# ASB.net
KiCad netlist of a schematic drawn in Altium Designer
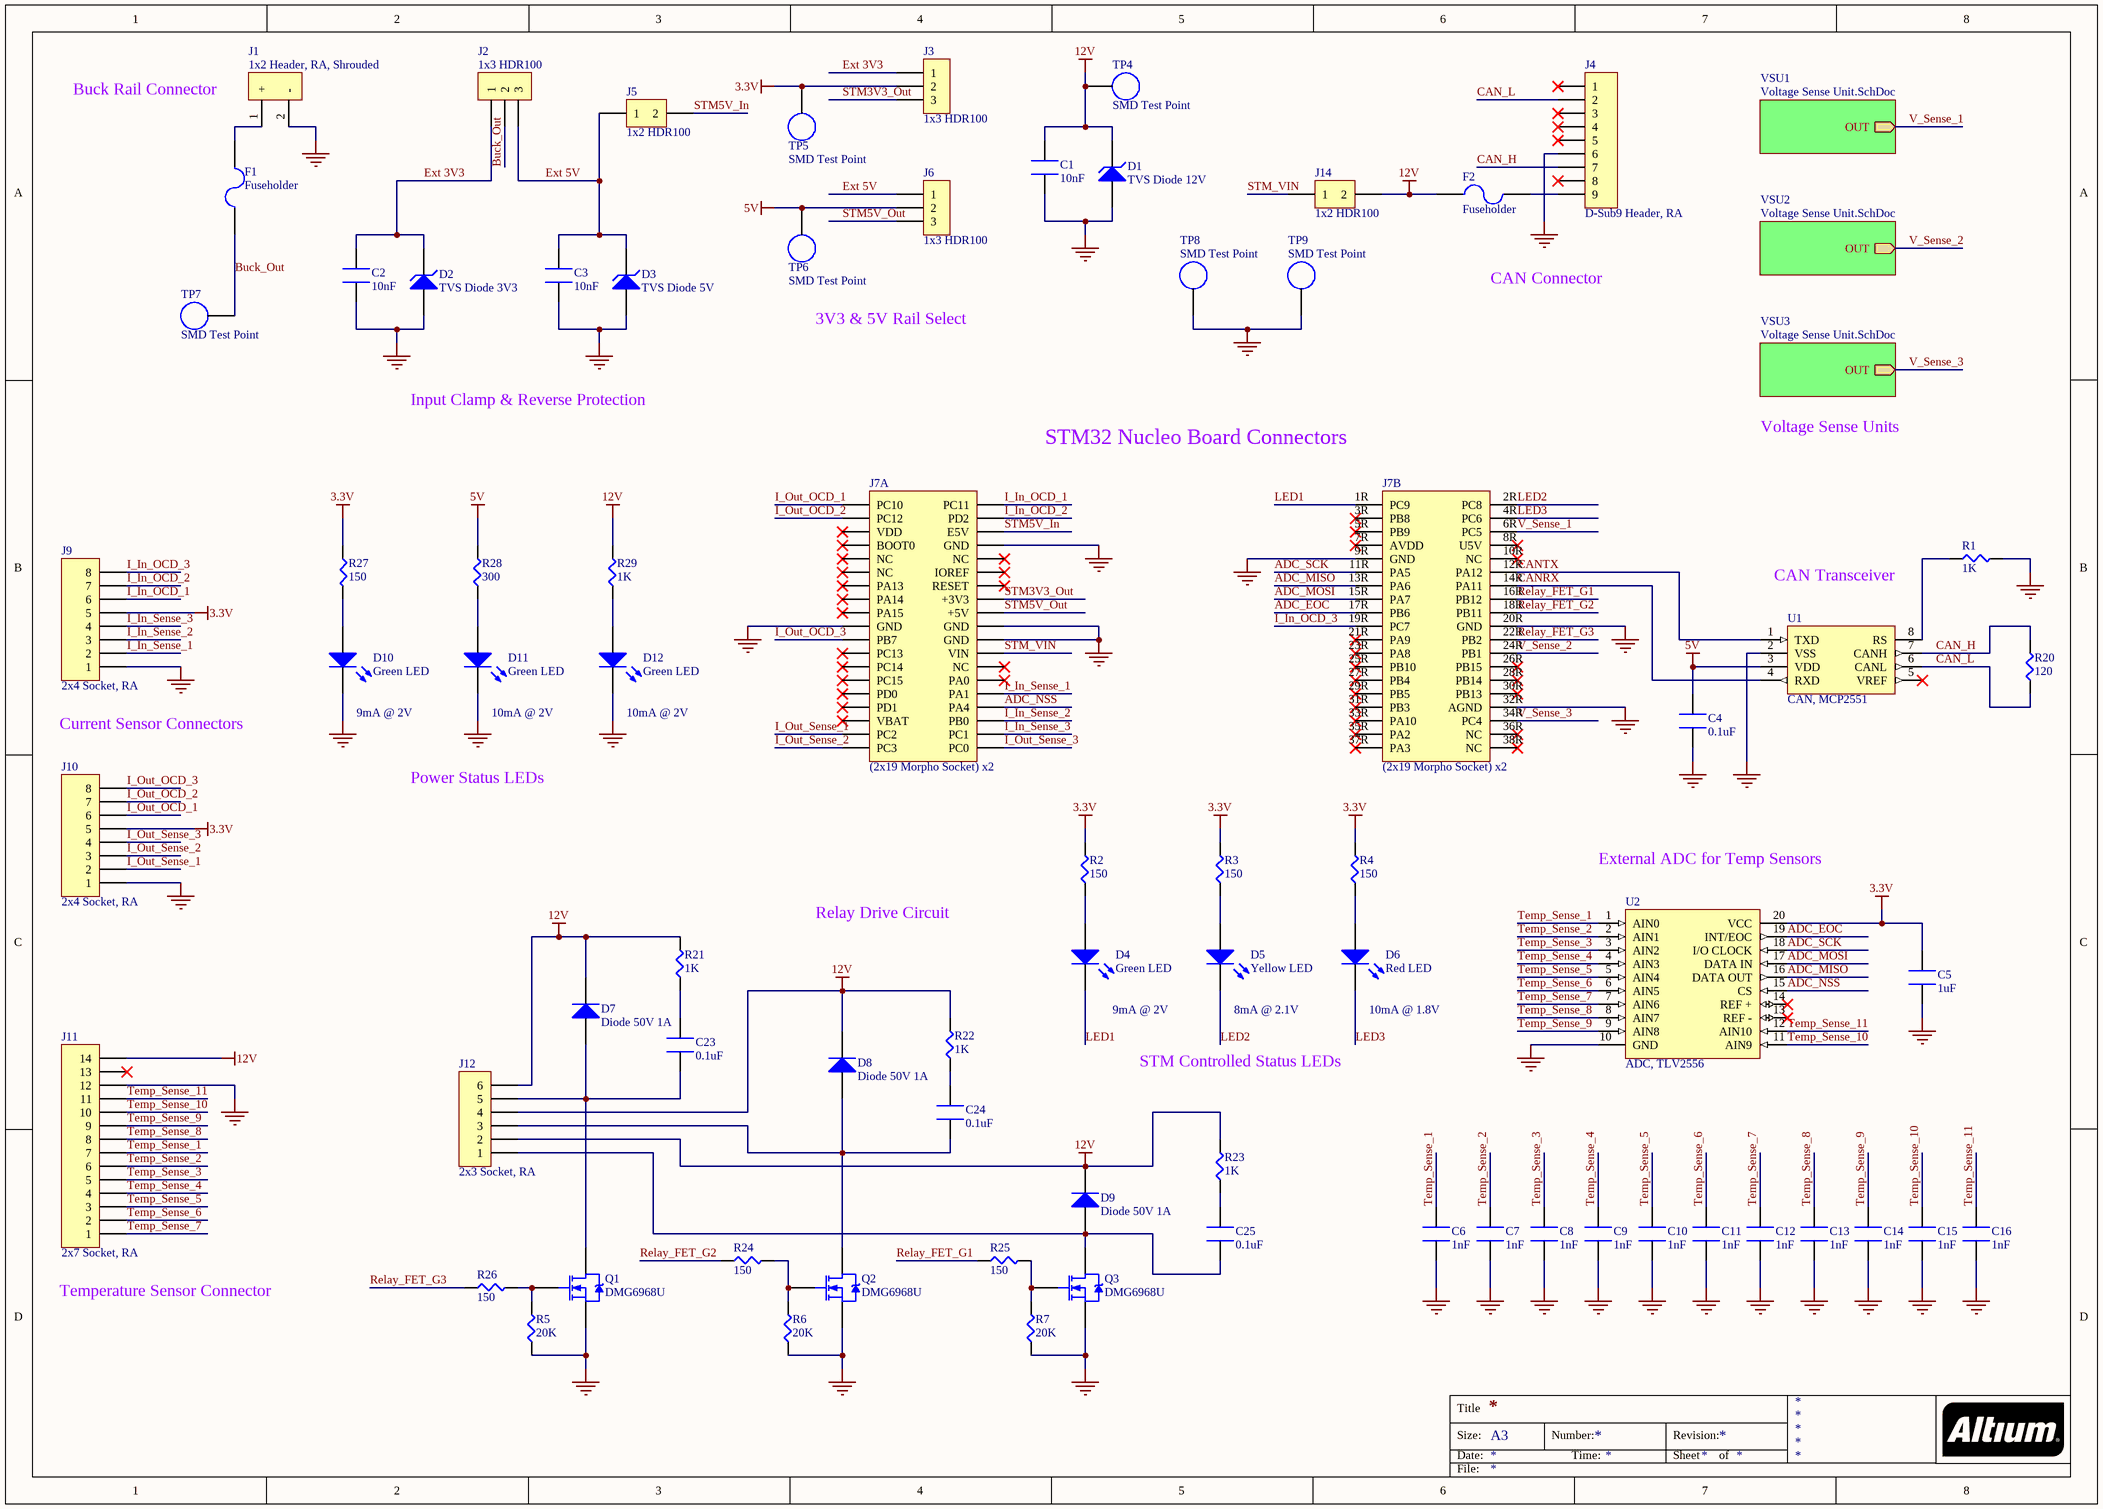
[diagram p0: ASB.SchDoc]

(export (version "E")
  (design (tool "Eeschema 10.0.6"))
  (components
    (comp (ref "C1")
      (value "10nF")
      (footprint "C0805")
      (description "Cap Ceramic 0.01uF 50V X7R 10% SMD 0805 125C Paper T/R")
      (fields
        (field (name "MANUFACTURER") "Samsung")
        (field (name "MANUFACTURER PART NUMBER") "CL21B103KBANNNC")
      )
      (libsource (lib "ASB") (part "CL21B103KBANNNC"))
    )
    (comp (ref "C2")
      (value "10nF")
      (footprint "C0805")
      (description "Cap Ceramic 0.01uF 50V X7R 10% SMD 0805 125C Paper T/R")
      (fields
        (field (name "MANUFACTURER") "Samsung")
        (field (name "MANUFACTURER PART NUMBER") "CL21B103KBANNNC")
      )
      (libsource (lib "ASB") (part "CL21B103KBANNNC"))
    )
    (comp (ref "C3")
      (value "10nF")
      (footprint "C0805")
      (description "Cap Ceramic 0.01uF 50V X7R 10% SMD 0805 125C Paper T/R")
      (fields
        (field (name "MANUFACTURER") "Samsung")
        (field (name "MANUFACTURER PART NUMBER") "CL21B103KBANNNC")
      )
      (libsource (lib "ASB") (part "CL21B103KBANNNC"))
    )
    (comp (ref "C4")
      (value "0.1uF")
      (footprint "C0805")
      (description "CAP CER 0.1UF 50V X7R 0805")
      (fields
        (field (name "MANUFACTURER") "Samsung")
        (field (name "MANUFACTURER PART NUMBER") "CL21B104KBCWPNC")
      )
      (libsource (lib "ASB") (part "CL21B104KBCWPNC"))
    )
    (comp (ref "C5")
      (value "1uF")
      (footprint "C0805")
      (description "Cap Ceramic 1uF 25V X7R 10% SMD 0805 125C T/R")
      (fields
        (field (name "MANUFACTURER") "Samsung")
        (field (name "MANUFACTURER PART NUMBER") "CL21B105KAFNNNE")
      )
      (libsource (lib "ASB") (part "CL21B105KAFNNNE"))
    )
    (comp (ref "C6")
      (value "1nF")
      (footprint "C0805")
      (description "CAP CER 0805 1NF 50V ULTRA STABL")
      (fields
        (field (name "MANUFACTURER") "KEMET")
        (field (name "MANUFACTURER PART NUMBER") "C0805C102J5HACAUTO")
      )
      (libsource (lib "ASB") (part "C0805C102J5HACAUTO"))
    )
    (comp (ref "C7")
      (value "1nF")
      (footprint "C0805")
      (description "CAP CER 0805 1NF 50V ULTRA STABL")
      (fields
        (field (name "MANUFACTURER") "KEMET")
        (field (name "MANUFACTURER PART NUMBER") "C0805C102J5HACAUTO")
      )
      (libsource (lib "ASB") (part "C0805C102J5HACAUTO"))
    )
    (comp (ref "C8")
      (value "1nF")
      (footprint "C0805")
      (description "CAP CER 0805 1NF 50V ULTRA STABL")
      (fields
        (field (name "MANUFACTURER") "KEMET")
        (field (name "MANUFACTURER PART NUMBER") "C0805C102J5HACAUTO")
      )
      (libsource (lib "ASB") (part "C0805C102J5HACAUTO"))
    )
    (comp (ref "C9")
      (value "1nF")
      (footprint "C0805")
      (description "CAP CER 0805 1NF 50V ULTRA STABL")
      (fields
        (field (name "MANUFACTURER") "KEMET")
        (field (name "MANUFACTURER PART NUMBER") "C0805C102J5HACAUTO")
      )
      (libsource (lib "ASB") (part "C0805C102J5HACAUTO"))
    )
    (comp (ref "C10")
      (value "1nF")
      (footprint "C0805")
      (description "CAP CER 0805 1NF 50V ULTRA STABL")
      (fields
        (field (name "MANUFACTURER") "KEMET")
        (field (name "MANUFACTURER PART NUMBER") "C0805C102J5HACAUTO")
      )
      (libsource (lib "ASB") (part "C0805C102J5HACAUTO"))
    )
    (comp (ref "C11")
      (value "1nF")
      (footprint "C0805")
      (description "CAP CER 0805 1NF 50V ULTRA STABL")
      (fields
        (field (name "MANUFACTURER") "KEMET")
        (field (name "MANUFACTURER PART NUMBER") "C0805C102J5HACAUTO")
      )
      (libsource (lib "ASB") (part "C0805C102J5HACAUTO"))
    )
    (comp (ref "C12")
      (value "1nF")
      (footprint "C0805")
      (description "CAP CER 0805 1NF 50V ULTRA STABL")
      (fields
        (field (name "MANUFACTURER") "KEMET")
        (field (name "MANUFACTURER PART NUMBER") "C0805C102J5HACAUTO")
      )
      (libsource (lib "ASB") (part "C0805C102J5HACAUTO"))
    )
    (comp (ref "C13")
      (value "1nF")
      (footprint "C0805")
      (description "CAP CER 0805 1NF 50V ULTRA STABL")
      (fields
        (field (name "MANUFACTURER") "KEMET")
        (field (name "MANUFACTURER PART NUMBER") "C0805C102J5HACAUTO")
      )
      (libsource (lib "ASB") (part "C0805C102J5HACAUTO"))
    )
    (comp (ref "C14")
      (value "1nF")
      (footprint "C0805")
      (description "CAP CER 0805 1NF 50V ULTRA STABL")
      (fields
        (field (name "MANUFACTURER") "KEMET")
        (field (name "MANUFACTURER PART NUMBER") "C0805C102J5HACAUTO")
      )
      (libsource (lib "ASB") (part "C0805C102J5HACAUTO"))
    )
    (comp (ref "C15")
      (value "1nF")
      (footprint "C0805")
      (description "CAP CER 0805 1NF 50V ULTRA STABL")
      (fields
        (field (name "MANUFACTURER") "KEMET")
        (field (name "MANUFACTURER PART NUMBER") "C0805C102J5HACAUTO")
      )
      (libsource (lib "ASB") (part "C0805C102J5HACAUTO"))
    )
    (comp (ref "C16")
      (value "1nF")
      (footprint "C0805")
      (description "CAP CER 0805 1NF 50V ULTRA STABL")
      (fields
        (field (name "MANUFACTURER") "KEMET")
        (field (name "MANUFACTURER PART NUMBER") "C0805C102J5HACAUTO")
      )
      (libsource (lib "ASB") (part "C0805C102J5HACAUTO"))
    )
    (comp (ref "C23")
      (value "0.1uF")
      (footprint "C0805")
      (description "CAP CER 0.1UF 50V X7R 0805")
      (fields
        (field (name "MANUFACTURER") "Samsung")
        (field (name "MANUFACTURER PART NUMBER") "CL21B104KBCWPNC")
      )
      (libsource (lib "ASB") (part "CL21B104KBCWPNC"))
    )
    (comp (ref "C24")
      (value "0.1uF")
      (footprint "C0805")
      (description "CAP CER 0.1UF 50V X7R 0805")
      (fields
        (field (name "MANUFACTURER") "Samsung")
        (field (name "MANUFACTURER PART NUMBER") "CL21B104KBCWPNC")
      )
      (libsource (lib "ASB") (part "CL21B104KBCWPNC"))
    )
    (comp (ref "C25")
      (value "0.1uF")
      (footprint "C0805")
      (description "CAP CER 0.1UF 50V X7R 0805")
      (fields
        (field (name "MANUFACTURER") "Samsung")
        (field (name "MANUFACTURER PART NUMBER") "CL21B104KBCWPNC")
      )
      (libsource (lib "ASB") (part "CL21B104KBCWPNC"))
    )
    (comp (ref "D1")
      (value "TVS Diode 12V")
      (footprint "SOD-323")
      (description "TVS DIODE 12V 19V SOD323")
      (fields
        (field (name "MANUFACTURER") "ON Semiconductor")
        (field (name "MANUFACTURER PART NUMBER") "SD12T1G")
      )
      (libsource (lib "ASB") (part "SD12T1G"))
    )
    (comp (ref "D2")
      (value "TVS Diode 3V3")
      (footprint "SOD-323")
      (description "ESD Suppressor TVS ±30kV 2-Pin SOD-323 T/R")
      (fields
        (field (name "MANUFACTURER") "Bourns")
        (field (name "MANUFACTURER PART NUMBER") "CDSOD323-T03S")
      )
      (libsource (lib "ASB") (part "CDSOD323-T03S"))
    )
    (comp (ref "D3")
      (value "TVS Diode 5V")
      (footprint "SOD-323")
      (description "TVS DIODE 5V 9.8V SOD323")
      (fields
        (field (name "MANUFACTURER") "ON Semiconductor")
        (field (name "MANUFACTURER PART NUMBER") "SD05T1G")
      )
      (libsource (lib "ASB") (part "SD05T1G"))
    )
    (comp (ref "D4")
      (value "Green LED")
      (footprint "L0805")
      (description "LED GREEN DIFFUSED SMD")
      (fields
        (field (name "MANUFACTURER") "Lumex")
        (field (name "MANUFACTURER PART NUMBER") "SML-LXT0805GW-TR")
      )
      (libsource (lib "ASB") (part "SML-LXT0805GW-TR"))
    )
    (comp (ref "D5")
      (value "Yellow LED")
      (footprint "L0805")
      (description "LED; Yellow; 10mcd; SMD; 100mA; 2.1V; 140deg; 585nm; Diffused; 5V; 50mW; -25degC")
      (fields
        (field (name "MANUFACTURER") "Lumex")
        (field (name "MANUFACTURER PART NUMBER") "SML-LXT0805YW-TR")
      )
      (libsource (lib "ASB") (part "SML-LXT0805YW-TR"))
    )
    (comp (ref "D6")
      (value "Red LED")
      (footprint "L0805")
      (description "LED RED DIFFUSED 0805 SMD")
      (fields
        (field (name "MANUFACTURER") "Lumex")
        (field (name "MANUFACTURER PART NUMBER") "SML-LXT0805SRW-TR")
      )
      (libsource (lib "ASB") (part "SML-LXT0805SRW-TR"))
    )
    (comp (ref "D7")
      (value "Diode 50V 1A")
      (footprint "CGRKM4001-HF")
      (description "DIODE GEN PURP 50V 1A SOD123F")
      (fields
        (field (name "MANUFACTURER") "Comchip")
        (field (name "MANUFACTURER PART NUMBER") "CGRKM4001-HF")
      )
      (libsource (lib "ASB") (part "CGRKM4001-HF"))
    )
    (comp (ref "D8")
      (value "Diode 50V 1A")
      (footprint "CGRKM4001-HF")
      (description "DIODE GEN PURP 50V 1A SOD123F")
      (fields
        (field (name "MANUFACTURER") "Comchip")
        (field (name "MANUFACTURER PART NUMBER") "CGRKM4001-HF")
      )
      (libsource (lib "ASB") (part "CGRKM4001-HF"))
    )
    (comp (ref "D9")
      (value "Diode 50V 1A")
      (footprint "CGRKM4001-HF")
      (description "DIODE GEN PURP 50V 1A SOD123F")
      (fields
        (field (name "MANUFACTURER") "Comchip")
        (field (name "MANUFACTURER PART NUMBER") "CGRKM4001-HF")
      )
      (libsource (lib "ASB") (part "CGRKM4001-HF"))
    )
    (comp (ref "D10")
      (value "Green LED")
      (footprint "L0805")
      (description "LED GREEN DIFFUSED SMD")
      (fields
        (field (name "MANUFACTURER") "Lumex")
        (field (name "MANUFACTURER PART NUMBER") "SML-LXT0805GW-TR")
      )
      (libsource (lib "ASB") (part "SML-LXT0805GW-TR"))
    )
    (comp (ref "D11")
      (value "Green LED")
      (footprint "L0805")
      (description "LED GREEN DIFFUSED SMD")
      (fields
        (field (name "MANUFACTURER") "Lumex")
        (field (name "MANUFACTURER PART NUMBER") "SML-LXT0805GW-TR")
      )
      (libsource (lib "ASB") (part "SML-LXT0805GW-TR"))
    )
    (comp (ref "D12")
      (value "Green LED")
      (footprint "L0805")
      (description "LED GREEN DIFFUSED SMD")
      (fields
        (field (name "MANUFACTURER") "Lumex")
        (field (name "MANUFACTURER PART NUMBER") "SML-LXT0805GW-TR")
      )
      (libsource (lib "ASB") (part "SML-LXT0805GW-TR"))
    )
    (comp (ref "F1")
      (value "Fuseholder")
      (footprint "SCHURTER - 0031.7701.11 - FUSE HOLDER, PCB MOUNT")
      (description "SCHURTER - 0031.7701.11 - FUSE HOLDER, PCB MOUNT")
      (fields
        (field (name "MANUFACTURER") "Schurter")
        (field (name "MANUFACTURER PART NUMBER") "0031.7701.11")
      )
      (libsource (lib "ASB") (part "0031.7701.11"))
    )
    (comp (ref "F2")
      (value "Fuseholder")
      (footprint "SCHURTER - 0031.7701.11 - FUSE HOLDER, PCB MOUNT")
      (description "SCHURTER - 0031.7701.11 - FUSE HOLDER, PCB MOUNT")
      (fields
        (field (name "MANUFACTURER") "Schurter")
        (field (name "MANUFACTURER PART NUMBER") "0031.7701.11")
      )
      (libsource (lib "ASB") (part "0031.7701.11"))
    )
    (comp (ref "J1")
      (value "1x2 Header, RA, Shrouded")
      (footprint "MOLEX_0705530001")
      (description "Headers & Wire Housings R/A HDR 2P low profile single")
      (fields (field (name "MANUFACTURER") "Molex") (field (name "MANUFACTURER PART NUMBER") "70553-0001"))
      (libsource (lib "ASB") (part "70553-0001"))
    )
    (comp (ref "J2")
      (value "1x3 HDR100")
      (footprint "MOLEX 0901200763")
      (description "CONN HEADER VERT 3POS 2.54MM")
      (fields (field (name "MANUFACTURER") "Molex") (field (name "MANUFACTURER PART NUMBER") "90120-0763"))
      (libsource (lib "") (part "0901200763_1"))
    )
    (comp (ref "J3")
      (value "1x3 HDR100")
      (footprint "MOLEX 0901200763")
      (description "CONN HEADER VERT 3POS 2.54MM")
      (fields (field (name "MANUFACTURER") "Molex") (field (name "MANUFACTURER PART NUMBER") "90120-0763"))
      (libsource (lib "ASB") (part "0901200763"))
    )
    (comp (ref "J4")
      (value "D-Sub9 Header, RA")
      (footprint "D9 Connector")
      (description "CONN D-SUB PLUG 9POS R/A SOLDER")
      (fields
        (field (name "MANUFACTURER") "TE Connectivity")
        (field (name "MANUFACTURER PART NUMBER") "5747840-6")
      )
      (libsource (lib "ASB") (part "5747840-6"))
    )
    (comp (ref "J5")
      (value "1x2 HDR100")
      (footprint "Molex 0901200762")
      (description "CONN HEADER VERT 2POS 2.54MM")
      (fields (field (name "MANUFACTURER") "Molex") (field (name "MANUFACTURER PART NUMBER") "0901200762"))
      (libsource (lib "ASB") (part "0901200762"))
    )
    (comp (ref "J6")
      (value "1x3 HDR100")
      (footprint "MOLEX 0901200763")
      (description "CONN HEADER VERT 3POS 2.54MM")
      (fields (field (name "MANUFACTURER") "Molex") (field (name "MANUFACTURER PART NUMBER") "90120-0763"))
      (libsource (lib "ASB") (part "0901200763"))
    )
    (comp (ref "J7")
      (value "(2x19 Morpho Socket) x2")
      (footprint "STM32 Nucleo Footprint]")
      (fields
        (field (name "MANUFACTURER") "Samtec")
        (field (name "MANUFACTURER PART NUMBER") "ESQ-119-24-T-D")
      )
      (libsource (lib "ASB") (part "STM32 Nucleo Connector"))
    )
    (comp (ref "J9")
      (value "2x4 Socket, RA")
      (footprint "Molex 105314 8 CON")
      (description "CONN HEADER R/A 8POS 2.5MM")
      (fields (field (name "MANUFACTURER") "Molex") (field (name "MANUFACTURER PART NUMBER") "1053141208"))
      (libsource (lib "ASB") (part "1053141208"))
    )
    (comp (ref "J10")
      (value "2x4 Socket, RA")
      (footprint "Molex 105314 8 CON")
      (description "CONN HEADER R/A 8POS 2.5MM")
      (fields (field (name "MANUFACTURER") "Molex") (field (name "MANUFACTURER PART NUMBER") "1053141208"))
      (libsource (lib "ASB") (part "1053141208"))
    )
    (comp (ref "J11")
      (value "2x7 Socket, RA")
      (footprint "MOLEX 105314 14 CON")
      (description "CONN HEADER R/A 14POS 2.5MM")
      (fields (field (name "MANUFACTURER") "Molex") (field (name "MANUFACTURER PART NUMBER") "1053141214"))
      (libsource (lib "ASB") (part "1053141214"))
    )
    (comp (ref "J12")
      (value "2x3 Socket, RA")
      (footprint "MOLEX 105314 6 CON")
      (description "CONN HEADER R/A 6POS 2.5MM")
      (fields (field (name "MANUFACTURER") "Molex") (field (name "MANUFACTURER PART NUMBER") "1053141206"))
      (libsource (lib "ASB") (part "1053141206"))
    )
    (comp (ref "J14")
      (value "1x2 HDR100")
      (footprint "Molex 0901200762")
      (description "CONN HEADER VERT 2POS 2.54MM")
      (fields (field (name "MANUFACTURER") "Molex") (field (name "MANUFACTURER PART NUMBER") "0901200762"))
      (libsource (lib "ASB") (part "0901200762"))
    )
    (comp (ref "Q1")
      (value "DMG6968U")
      (footprint "MOSFET DMG6968UDICT-ND")
      (description "MOSFET N-CH 20V 6.5A SOT-23")
      (fields (field (name "MANUFACTURER") "Diodes") (field (name "MANUFACTURER PART NUMBER") "DMG6968U-7"))
      (libsource (lib "ASB") (part "DMG6968U-7"))
    )
    (comp (ref "Q2")
      (value "DMG6968U")
      (footprint "MOSFET DMG6968UDICT-ND")
      (description "MOSFET N-CH 20V 6.5A SOT-23")
      (fields (field (name "MANUFACTURER") "Diodes") (field (name "MANUFACTURER PART NUMBER") "DMG6968U-7"))
      (libsource (lib "ASB") (part "DMG6968U-7"))
    )
    (comp (ref "Q3")
      (value "DMG6968U")
      (footprint "MOSFET DMG6968UDICT-ND")
      (description "MOSFET N-CH 20V 6.5A SOT-23")
      (fields (field (name "MANUFACTURER") "Diodes") (field (name "MANUFACTURER PART NUMBER") "DMG6968U-7"))
      (libsource (lib "ASB") (part "DMG6968U-7"))
    )
    (comp (ref "R1")
      (value "1K")
      (footprint "R0805")
      (description "RES SMD 1K OHM 1% 1/8W 0805")
      (fields
        (field (name "MANUFACTURER") "Panasonic")
        (field (name "MANUFACTURER PART NUMBER") "ERJ6ENF1001V")
      )
      (libsource (lib "ASB") (part "ERJ6ENF1001V"))
    )
    (comp (ref "R2")
      (value "150")
      (footprint "R0805")
      (description "RES SMD 150 OHM 1% 1/8W 0805")
      (fields
        (field (name "MANUFACTURER") "Panasonic")
        (field (name "MANUFACTURER PART NUMBER") "ERJ6ENF1500V")
      )
      (libsource (lib "ASB") (part "ERJ6ENF1500V"))
    )
    (comp (ref "R3")
      (value "150")
      (footprint "R0805")
      (description "RES SMD 150 OHM 1% 1/8W 0805")
      (fields
        (field (name "MANUFACTURER") "Panasonic")
        (field (name "MANUFACTURER PART NUMBER") "ERJ6ENF1500V")
      )
      (libsource (lib "ASB") (part "ERJ6ENF1500V"))
    )
    (comp (ref "R4")
      (value "150")
      (footprint "R0805")
      (description "RES SMD 150 OHM 1% 1/8W 0805")
      (fields
        (field (name "MANUFACTURER") "Panasonic")
        (field (name "MANUFACTURER PART NUMBER") "ERJ6ENF1500V")
      )
      (libsource (lib "ASB") (part "ERJ6ENF1500V"))
    )
    (comp (ref "R5")
      (value "20K")
      (footprint "R0805")
      (description "RES SMD 20K OHM 1% 1/8W 0805")
      (fields
        (field (name "MANUFACTURER") "Panasonic")
        (field (name "MANUFACTURER PART NUMBER") "ERJ6ENF2002V")
      )
      (libsource (lib "ASB") (part "ERJ6ENF2002V"))
    )
    (comp (ref "R6")
      (value "20K")
      (footprint "R0805")
      (description "RES SMD 20K OHM 1% 1/8W 0805")
      (fields
        (field (name "MANUFACTURER") "Panasonic")
        (field (name "MANUFACTURER PART NUMBER") "ERJ6ENF2002V")
      )
      (libsource (lib "ASB") (part "ERJ6ENF2002V"))
    )
    (comp (ref "R7")
      (value "20K")
      (footprint "R0805")
      (description "RES SMD 20K OHM 1% 1/8W 0805")
      (fields
        (field (name "MANUFACTURER") "Panasonic")
        (field (name "MANUFACTURER PART NUMBER") "ERJ6ENF2002V")
      )
      (libsource (lib "ASB") (part "ERJ6ENF2002V"))
    )
    (comp (ref "R20")
      (value "120")
      (footprint "R0805")
      (description "RES SMD 120 OHM 1% 1/8W 0805")
      (fields
        (field (name "MANUFACTURER") "Panasonic")
        (field (name "MANUFACTURER PART NUMBER") "ERJ6ENF1200V")
      )
      (libsource (lib "ASB") (part "ERJ6ENF1200V"))
    )
    (comp (ref "R21")
      (value "1K")
      (footprint "R0805")
      (description "RES SMD 1K OHM 1% 1/8W 0805")
      (fields
        (field (name "MANUFACTURER") "Panasonic")
        (field (name "MANUFACTURER PART NUMBER") "ERJ6ENF1001V")
      )
      (libsource (lib "ASB") (part "ERJ6ENF1001V"))
    )
    (comp (ref "R22")
      (value "1K")
      (footprint "R0805")
      (description "RES SMD 1K OHM 1% 1/8W 0805")
      (fields
        (field (name "MANUFACTURER") "Panasonic")
        (field (name "MANUFACTURER PART NUMBER") "ERJ6ENF1001V")
      )
      (libsource (lib "ASB") (part "ERJ6ENF1001V"))
    )
    (comp (ref "R23")
      (value "1K")
      (footprint "R0805")
      (description "RES SMD 1K OHM 1% 1/8W 0805")
      (fields
        (field (name "MANUFACTURER") "Panasonic")
        (field (name "MANUFACTURER PART NUMBER") "ERJ6ENF1001V")
      )
      (libsource (lib "ASB") (part "ERJ6ENF1001V"))
    )
    (comp (ref "R24")
      (value "150")
      (footprint "R0805")
      (description "RES SMD 150 OHM 1% 1/8W 0805")
      (fields
        (field (name "MANUFACTURER") "Panasonic")
        (field (name "MANUFACTURER PART NUMBER") "ERJ6ENF1500V")
      )
      (libsource (lib "ASB") (part "ERJ6ENF1500V"))
    )
    (comp (ref "R25")
      (value "150")
      (footprint "R0805")
      (description "RES SMD 150 OHM 1% 1/8W 0805")
      (fields
        (field (name "MANUFACTURER") "Panasonic")
        (field (name "MANUFACTURER PART NUMBER") "ERJ6ENF1500V")
      )
      (libsource (lib "ASB") (part "ERJ6ENF1500V"))
    )
    (comp (ref "R26")
      (value "150")
      (footprint "R0805")
      (description "RES SMD 150 OHM 1% 1/8W 0805")
      (fields
        (field (name "MANUFACTURER") "Panasonic")
        (field (name "MANUFACTURER PART NUMBER") "ERJ6ENF1500V")
      )
      (libsource (lib "ASB") (part "ERJ6ENF1500V"))
    )
    (comp (ref "R27")
      (value "150")
      (footprint "R0805")
      (description "RES SMD 150 OHM 1% 1/8W 0805")
      (fields
        (field (name "MANUFACTURER") "Panasonic")
        (field (name "MANUFACTURER PART NUMBER") "ERJ6ENF1500V")
      )
      (libsource (lib "ASB") (part "ERJ6ENF1500V"))
    )
    (comp (ref "R28")
      (value "300")
      (footprint "R0805")
      (description "RES SMD 300 OHM 1% 1/8W 0805")
      (fields
        (field (name "MANUFACTURER") "Panasonic")
        (field (name "MANUFACTURER PART NUMBER") "ERJ-6ENF3000V")
      )
      (libsource (lib "ASB") (part "ERJ-6ENF3000V"))
    )
    (comp (ref "R29")
      (value "1K")
      (footprint "R0805")
      (description "RES SMD 1K OHM 1% 1/8W 0805")
      (fields
        (field (name "MANUFACTURER") "Panasonic")
        (field (name "MANUFACTURER PART NUMBER") "ERJ6ENF1001V")
      )
      (libsource (lib "ASB") (part "ERJ6ENF1001V"))
    )
    (comp (ref "TP4")
      (value "SMD Test Point")
      (footprint "5019 Keystone SMT Test Point")
      (description "Phosphor Bronze Contact Miniature Silver Plated Surface Mount Test Points")
      (fields
        (field (name "MANUFACTURER") "Keystone Electronics")
        (field (name "MANUFACTURER PART NUMBER") "5019")
      )
      (libsource (lib "ASB") (part "5019"))
    )
    (comp (ref "TP5")
      (value "SMD Test Point")
      (footprint "5019 Keystone SMT Test Point")
      (description "Phosphor Bronze Contact Miniature Silver Plated Surface Mount Test Points")
      (fields
        (field (name "MANUFACTURER") "Keystone Electronics")
        (field (name "MANUFACTURER PART NUMBER") "5019")
      )
      (libsource (lib "ASB") (part "5019"))
    )
    (comp (ref "TP6")
      (value "SMD Test Point")
      (footprint "5019 Keystone SMT Test Point")
      (description "Phosphor Bronze Contact Miniature Silver Plated Surface Mount Test Points")
      (fields
        (field (name "MANUFACTURER") "Keystone Electronics")
        (field (name "MANUFACTURER PART NUMBER") "5019")
      )
      (libsource (lib "ASB") (part "5019"))
    )
    (comp (ref "TP7")
      (value "SMD Test Point")
      (footprint "5019 Keystone SMT Test Point")
      (description "Phosphor Bronze Contact Miniature Silver Plated Surface Mount Test Points")
      (fields
        (field (name "MANUFACTURER") "Keystone Electronics")
        (field (name "MANUFACTURER PART NUMBER") "5019")
      )
      (libsource (lib "ASB") (part "5019"))
    )
    (comp (ref "TP8")
      (value "SMD Test Point")
      (footprint "5019 Keystone SMT Test Point")
      (description "Phosphor Bronze Contact Miniature Silver Plated Surface Mount Test Points")
      (fields
        (field (name "MANUFACTURER") "Keystone Electronics")
        (field (name "MANUFACTURER PART NUMBER") "5019")
      )
      (libsource (lib "ASB") (part "5019"))
    )
    (comp (ref "TP9")
      (value "SMD Test Point")
      (footprint "5019 Keystone SMT Test Point")
      (description "Phosphor Bronze Contact Miniature Silver Plated Surface Mount Test Points")
      (fields
        (field (name "MANUFACTURER") "Keystone Electronics")
        (field (name "MANUFACTURER PART NUMBER") "5019")
      )
      (libsource (lib "ASB") (part "5019"))
    )
    (comp (ref "U1")
      (value "CAN, MCP2551")
      (footprint "LT1677IS8#TRPBF")
      (description "IC, TRANSCEIVER, CAN, SMD, 8SOIC")
      (fields
        (field (name "MANUFACTURER") "Microchip")
        (field (name "MANUFACTURER PART NUMBER") "MCP2551-E/SN")
      )
      (libsource (lib "ASB") (part "MCP2551-E/SN"))
    )
    (comp (ref "U2")
      (value "ADC, TLV2556")
      (footprint "DW20-L")
      (description "IC SERIAL ADC 12-BIT 5V 20-SOIC")
      (fields
        (field (name "MANUFACTURER") "Texas Instruments")
        (field (name "MANUFACTURER PART NUMBER") "TLV2556IDW")
      )
      (libsource (lib "ASB") (part "TLV2556IDW"))
    )
  )
  (nets
    (net (code "1") (name "/ADC_EOC") (class "Default")
      (node (ref "J7") (pin "17R") (pinfunction "PB6_17R") (pintype "passive"))
      (node (ref "U2") (pin "19") (pinfunction "INT/EOC_19") (pintype "output"))
    )
    (net (code "2") (name "/ADC_MISO") (class "Default")
      (node (ref "J7") (pin "13R") (pinfunction "PA6_13R") (pintype "passive"))
      (node (ref "U2") (pin "16") (pinfunction "DATA_OUT_16") (pintype "output"))
    )
    (net (code "3") (name "/ADC_MOSI") (class "Default")
      (node (ref "J7") (pin "15R") (pinfunction "PA7_15R") (pintype "passive"))
      (node (ref "U2") (pin "17") (pinfunction "DATA_IN_17") (pintype "input"))
    )
    (net (code "4") (name "/ADC_NSS") (class "Default")
      (node (ref "J7") (pin "32L") (pinfunction "PA4_32L") (pintype "passive"))
      (node (ref "U2") (pin "15") (pinfunction "CS_15") (pintype "input"))
    )
    (net (code "5") (name "/ADC_SCK") (class "Default")
      (node (ref "J7") (pin "11R") (pinfunction "PA5_11R") (pintype "passive"))
      (node (ref "U2") (pin "18") (pinfunction "I/O_CLOCK_18") (pintype "input"))
    )
    (net (code "6") (name "/Buck_Out") (class "Default")
      (node (ref "F1") (pin "2") (pinfunction "2_2") (pintype "passive"))
      (node (ref "J2") (pin "2") (pinfunction "2_2") (pintype "passive"))
      (node (ref "TP7") (pin "1") (pinfunction "1_1") (pintype "passive"))
    )
    (net (code "7") (name "/CANRX") (class "Default")
      (node (ref "J7") (pin "14R") (pinfunction "PA11_14R") (pintype "passive"))
      (node (ref "U1") (pin "4") (pinfunction "RXD_4") (pintype "output"))
    )
    (net (code "8") (name "/CANTX") (class "Default")
      (node (ref "J7") (pin "12R") (pinfunction "PA12_12R") (pintype "passive"))
      (node (ref "U1") (pin "1") (pinfunction "TXD_1") (pintype "input"))
    )
    (net (code "9") (name "/CAN_H") (class "Default")
      (node (ref "J4") (pin "7") (pinfunction "7_7") (pintype "passive"))
      (node (ref "R20") (pin "2") (pinfunction "2_2") (pintype "passive"))
      (node (ref "U1") (pin "7") (pinfunction "CANH_7") (pintype "output"))
    )
    (net (code "10") (name "/CAN_L") (class "Default")
      (node (ref "J4") (pin "2") (pinfunction "2_2") (pintype "passive"))
      (node (ref "R20") (pin "1") (pinfunction "1_1") (pintype "passive"))
      (node (ref "U1") (pin "6") (pinfunction "CANL_6") (pintype "output"))
    )
    (net (code "11") (name "/Ext 3V3") (class "Default")
      (node (ref "C2") (pin "2") (pinfunction "2_2") (pintype "passive"))
      (node (ref "D2") (pin "2") (pinfunction "K_2") (pintype "passive"))
      (node (ref "J2") (pin "1") (pinfunction "1_1") (pintype "passive"))
      (node (ref "J3") (pin "1") (pinfunction "1_1") (pintype "passive"))
    )
    (net (code "12") (name "/Ext 5V") (class "Default")
      (node (ref "C3") (pin "2") (pinfunction "2_2") (pintype "passive"))
      (node (ref "D3") (pin "2") (pinfunction "K_2") (pintype "passive"))
      (node (ref "J2") (pin "3") (pinfunction "3_3") (pintype "passive"))
      (node (ref "J5") (pin "1") (pinfunction "1_1") (pintype "passive"))
      (node (ref "J6") (pin "1") (pinfunction "1_1") (pintype "passive"))
    )
    (net (code "13") (name "/I_In_OCD_1") (class "Default")
      (node (ref "J7") (pin "2L") (pinfunction "PC11_2L") (pintype "passive"))
      (node (ref "J9") (pin "6") (pinfunction "6_6") (pintype "passive"))
    )
    (net (code "14") (name "/I_In_OCD_2") (class "Default")
      (node (ref "J7") (pin "4L") (pinfunction "PD2_4L") (pintype "passive"))
      (node (ref "J9") (pin "7") (pinfunction "7_7") (pintype "passive"))
    )
    (net (code "15") (name "/I_In_OCD_3") (class "Default")
      (node (ref "J7") (pin "19R") (pinfunction "PC7_19R") (pintype "passive"))
      (node (ref "J9") (pin "8") (pinfunction "8_8") (pintype "passive"))
    )
    (net (code "16") (name "/I_In_Sense_1") (class "Default")
      (node (ref "J7") (pin "30L") (pinfunction "PA1_30L") (pintype "passive"))
      (node (ref "J9") (pin "2") (pinfunction "2_2") (pintype "passive"))
    )
    (net (code "17") (name "/I_In_Sense_2") (class "Default")
      (node (ref "J7") (pin "34L") (pinfunction "PB0_34L") (pintype "passive"))
      (node (ref "J9") (pin "3") (pinfunction "3_3") (pintype "passive"))
    )
    (net (code "18") (name "/I_In_Sense_3") (class "Default")
      (node (ref "J7") (pin "36L") (pinfunction "PC1_36L") (pintype "passive"))
      (node (ref "J9") (pin "4") (pinfunction "4_4") (pintype "passive"))
    )
    (net (code "19") (name "/I_Out_OCD_1") (class "Default")
      (node (ref "J10") (pin "6") (pinfunction "6_6") (pintype "passive"))
      (node (ref "J7") (pin "1L") (pinfunction "PC10_1L") (pintype "passive"))
    )
    (net (code "20") (name "/I_Out_OCD_2") (class "Default")
      (node (ref "J10") (pin "7") (pinfunction "7_7") (pintype "passive"))
      (node (ref "J7") (pin "3L") (pinfunction "PC12_3L") (pintype "passive"))
    )
    (net (code "21") (name "/I_Out_OCD_3") (class "Default")
      (node (ref "J10") (pin "8") (pinfunction "8_8") (pintype "passive"))
      (node (ref "J7") (pin "21L") (pinfunction "PB7_21L") (pintype "passive"))
    )
    (net (code "22") (name "/I_Out_Sense_1") (class "Default")
      (node (ref "J10") (pin "2") (pinfunction "2_2") (pintype "passive"))
      (node (ref "J7") (pin "35L") (pinfunction "PC2_35L") (pintype "passive"))
    )
    (net (code "23") (name "/I_Out_Sense_2") (class "Default")
      (node (ref "J10") (pin "3") (pinfunction "3_3") (pintype "passive"))
      (node (ref "J7") (pin "37L") (pinfunction "PC3_37L") (pintype "passive"))
    )
    (net (code "24") (name "/I_Out_Sense_3") (class "Default")
      (node (ref "J10") (pin "4") (pinfunction "4_4") (pintype "passive"))
      (node (ref "J7") (pin "38L") (pinfunction "PC0_38L") (pintype "passive"))
    )
    (net (code "25") (name "/LED1") (class "Default")
      (node (ref "D4") (pin "2") (pinfunction "K_2") (pintype "passive"))
      (node (ref "J7") (pin "1R") (pinfunction "PC9_1R") (pintype "passive"))
    )
    (net (code "26") (name "/LED2") (class "Default")
      (node (ref "D5") (pin "2") (pinfunction "K_2") (pintype "passive"))
      (node (ref "J7") (pin "2R") (pinfunction "PC8_2R") (pintype "passive"))
    )
    (net (code "27") (name "/LED3") (class "Default")
      (node (ref "D6") (pin "2") (pinfunction "K_2") (pintype "passive"))
      (node (ref "J7") (pin "4R") (pinfunction "PC6_4R") (pintype "passive"))
    )
    (net (code "28") (name "/Relay_FET_G1") (class "Default")
      (node (ref "J7") (pin "16R") (pinfunction "PB12_16R") (pintype "passive"))
      (node (ref "R25") (pin "1") (pinfunction "1_1") (pintype "passive"))
    )
    (net (code "29") (name "/Relay_FET_G2") (class "Default")
      (node (ref "J7") (pin "18R") (pinfunction "PB11_18R") (pintype "passive"))
      (node (ref "R24") (pin "1") (pinfunction "1_1") (pintype "passive"))
    )
    (net (code "30") (name "/Relay_FET_G3") (class "Default")
      (node (ref "J7") (pin "22R") (pinfunction "PB2_22R") (pintype "passive"))
      (node (ref "R26") (pin "1") (pinfunction "1_1") (pintype "passive"))
    )
    (net (code "31") (name "/STM3V3_Out") (class "Default")
      (node (ref "J3") (pin "3") (pinfunction "3_3") (pintype "passive"))
      (node (ref "J7") (pin "16L") (pinfunction "+3V3_16L") (pintype "passive"))
    )
    (net (code "32") (name "/STM5V_In") (class "Default")
      (node (ref "J5") (pin "2") (pinfunction "2_2") (pintype "passive"))
      (node (ref "J7") (pin "6L") (pinfunction "E5V_6L") (pintype "passive"))
    )
    (net (code "33") (name "/STM5V_Out") (class "Default")
      (node (ref "J6") (pin "3") (pinfunction "3_3") (pintype "passive"))
      (node (ref "J7") (pin "18L") (pinfunction "+5V_18L") (pintype "passive"))
    )
    (net (code "34") (name "/STM_VIN") (class "Default")
      (node (ref "J14") (pin "1") (pinfunction "1_1") (pintype "passive"))
      (node (ref "J7") (pin "24L") (pinfunction "VIN_24L") (pintype "passive"))
    )
    (net (code "35") (name "/Temp_Sense_1") (class "Default")
      (node (ref "C6") (pin "2") (pinfunction "2_2") (pintype "passive"))
      (node (ref "J11") (pin "7") (pinfunction "7_7") (pintype "passive"))
      (node (ref "U2") (pin "1") (pinfunction "AIN0_1") (pintype "input"))
    )
    (net (code "36") (name "/Temp_Sense_2") (class "Default")
      (node (ref "C7") (pin "2") (pinfunction "2_2") (pintype "passive"))
      (node (ref "J11") (pin "6") (pinfunction "6_6") (pintype "passive"))
      (node (ref "U2") (pin "2") (pinfunction "AIN1_2") (pintype "input"))
    )
    (net (code "37") (name "/Temp_Sense_3") (class "Default")
      (node (ref "C8") (pin "2") (pinfunction "2_2") (pintype "passive"))
      (node (ref "J11") (pin "5") (pinfunction "5_5") (pintype "passive"))
      (node (ref "U2") (pin "3") (pinfunction "AIN2_3") (pintype "input"))
    )
    (net (code "38") (name "/Temp_Sense_4") (class "Default")
      (node (ref "C9") (pin "2") (pinfunction "2_2") (pintype "passive"))
      (node (ref "J11") (pin "4") (pinfunction "4_4") (pintype "passive"))
      (node (ref "U2") (pin "4") (pinfunction "AIN3_4") (pintype "input"))
    )
    (net (code "39") (name "/Temp_Sense_5") (class "Default")
      (node (ref "C10") (pin "2") (pinfunction "2_2") (pintype "passive"))
      (node (ref "J11") (pin "3") (pinfunction "3_3") (pintype "passive"))
      (node (ref "U2") (pin "5") (pinfunction "AIN4_5") (pintype "input"))
    )
    (net (code "40") (name "/Temp_Sense_6") (class "Default")
      (node (ref "C11") (pin "2") (pinfunction "2_2") (pintype "passive"))
      (node (ref "J11") (pin "2") (pinfunction "2_2") (pintype "passive"))
      (node (ref "U2") (pin "6") (pinfunction "AIN5_6") (pintype "input"))
    )
    (net (code "41") (name "/Temp_Sense_7") (class "Default")
      (node (ref "C12") (pin "2") (pinfunction "2_2") (pintype "passive"))
      (node (ref "J11") (pin "1") (pinfunction "1_1") (pintype "passive"))
      (node (ref "U2") (pin "7") (pinfunction "AIN6_7") (pintype "input"))
    )
    (net (code "42") (name "/Temp_Sense_8") (class "Default")
      (node (ref "C13") (pin "2") (pinfunction "2_2") (pintype "passive"))
      (node (ref "J11") (pin "8") (pinfunction "8_8") (pintype "passive"))
      (node (ref "U2") (pin "8") (pinfunction "AIN7_8") (pintype "input"))
    )
    (net (code "43") (name "/Temp_Sense_9") (class "Default")
      (node (ref "C14") (pin "2") (pinfunction "2_2") (pintype "passive"))
      (node (ref "J11") (pin "9") (pinfunction "9_9") (pintype "passive"))
      (node (ref "U2") (pin "9") (pinfunction "AIN8_9") (pintype "input"))
    )
    (net (code "44") (name "/Temp_Sense_10") (class "Default")
      (node (ref "C15") (pin "2") (pinfunction "2_2") (pintype "passive"))
      (node (ref "J11") (pin "10") (pinfunction "10_10") (pintype "passive"))
      (node (ref "U2") (pin "11") (pinfunction "AIN9_11") (pintype "input"))
    )
    (net (code "45") (name "/Temp_Sense_11") (class "Default")
      (node (ref "C16") (pin "2") (pinfunction "2_2") (pintype "passive"))
      (node (ref "J11") (pin "11") (pinfunction "11_11") (pintype "passive"))
      (node (ref "U2") (pin "12") (pinfunction "AIN10_12") (pintype "input"))
    )
    (net (code "46") (name "/V_Sense_1") (class "Default")
      (node (ref "J7") (pin "6R") (pinfunction "PC5_6R") (pintype "passive"))
    )
    (net (code "47") (name "/V_Sense_2") (class "Default")
      (node (ref "J7") (pin "24R") (pinfunction "PB1_24R") (pintype "passive"))
    )
    (net (code "48") (name "/V_Sense_3") (class "Default")
      (node (ref "J7") (pin "34R") (pinfunction "PC4_34R") (pintype "passive"))
    )
    (net (code "49") (name "3.3V") (class "Default")
      (node (ref "C5") (pin "2") (pinfunction "2_2") (pintype "passive"))
      (node (ref "J10") (pin "5") (pinfunction "5_5") (pintype "passive"))
      (node (ref "J3") (pin "2") (pinfunction "2_2") (pintype "passive"))
      (node (ref "J9") (pin "5") (pinfunction "5_5") (pintype "passive"))
      (node (ref "R2") (pin "2") (pinfunction "2_2") (pintype "passive"))
      (node (ref "R27") (pin "1") (pinfunction "1_1") (pintype "passive"))
      (node (ref "R3") (pin "2") (pinfunction "2_2") (pintype "passive"))
      (node (ref "R4") (pin "2") (pinfunction "2_2") (pintype "passive"))
      (node (ref "TP5") (pin "1") (pinfunction "1_1") (pintype "passive"))
      (node (ref "U2") (pin "20") (pinfunction "VCC_20") (pintype "power_in"))
    )
    (net (code "50") (name "5V") (class "Default")
      (node (ref "C4") (pin "2") (pinfunction "2_2") (pintype "passive"))
      (node (ref "J6") (pin "2") (pinfunction "2_2") (pintype "passive"))
      (node (ref "R28") (pin "2") (pinfunction "2_2") (pintype "passive"))
      (node (ref "TP6") (pin "1") (pinfunction "1_1") (pintype "passive"))
      (node (ref "U1") (pin "3") (pinfunction "VDD_3") (pintype "power_in"))
    )
    (net (code "51") (name "12V") (class "Default")
      (node (ref "C1") (pin "2") (pinfunction "2_2") (pintype "passive"))
      (node (ref "D1") (pin "2") (pinfunction "K_2") (pintype "passive"))
      (node (ref "D7") (pin "2") (pinfunction "K_2") (pintype "passive"))
      (node (ref "D8") (pin "2") (pinfunction "K_2") (pintype "passive"))
      (node (ref "D9") (pin "2") (pinfunction "K_2") (pintype "passive"))
      (node (ref "F2") (pin "1") (pinfunction "1_1") (pintype "passive"))
      (node (ref "J11") (pin "14") (pinfunction "14_14") (pintype "passive"))
      (node (ref "J12") (pin "2") (pinfunction "2_2") (pintype "passive"))
      (node (ref "J12") (pin "4") (pinfunction "4_4") (pintype "passive"))
      (node (ref "J12") (pin "6") (pinfunction "6_6") (pintype "passive"))
      (node (ref "J14") (pin "2") (pinfunction "2_2") (pintype "passive"))
      (node (ref "R21") (pin "2") (pinfunction "2_2") (pintype "passive"))
      (node (ref "R22") (pin "2") (pinfunction "2_2") (pintype "passive"))
      (node (ref "R23") (pin "2") (pinfunction "2_2") (pintype "passive"))
      (node (ref "R29") (pin "2") (pinfunction "2_2") (pintype "passive"))
      (node (ref "TP4") (pin "1") (pinfunction "1_1") (pintype "passive"))
    )
    (net (code "52") (name "GND") (class "Default")
      (node (ref "C1") (pin "1") (pinfunction "1_1") (pintype "passive"))
      (node (ref "C10") (pin "1") (pinfunction "1_1") (pintype "passive"))
      (node (ref "C11") (pin "1") (pinfunction "1_1") (pintype "passive"))
      (node (ref "C12") (pin "1") (pinfunction "1_1") (pintype "passive"))
      (node (ref "C13") (pin "1") (pinfunction "1_1") (pintype "passive"))
      (node (ref "C14") (pin "1") (pinfunction "1_1") (pintype "passive"))
      (node (ref "C15") (pin "1") (pinfunction "1_1") (pintype "passive"))
      (node (ref "C16") (pin "1") (pinfunction "1_1") (pintype "passive"))
      (node (ref "C2") (pin "1") (pinfunction "1_1") (pintype "passive"))
      (node (ref "C3") (pin "1") (pinfunction "1_1") (pintype "passive"))
      (node (ref "C4") (pin "1") (pinfunction "1_1") (pintype "passive"))
      (node (ref "C5") (pin "1") (pinfunction "1_1") (pintype "passive"))
      (node (ref "C6") (pin "1") (pinfunction "1_1") (pintype "passive"))
      (node (ref "C7") (pin "1") (pinfunction "1_1") (pintype "passive"))
      (node (ref "C8") (pin "1") (pinfunction "1_1") (pintype "passive"))
      (node (ref "C9") (pin "1") (pinfunction "1_1") (pintype "passive"))
      (node (ref "D1") (pin "1") (pinfunction "A_1") (pintype "passive"))
      (node (ref "D10") (pin "2") (pinfunction "K_2") (pintype "passive"))
      (node (ref "D11") (pin "2") (pinfunction "K_2") (pintype "passive"))
      (node (ref "D12") (pin "2") (pinfunction "K_2") (pintype "passive"))
      (node (ref "D2") (pin "1") (pinfunction "A_1") (pintype "passive"))
      (node (ref "D3") (pin "1") (pinfunction "A_1") (pintype "passive"))
      (node (ref "J1") (pin "2") (pinfunction "-_2") (pintype "passive"))
      (node (ref "J10") (pin "1") (pinfunction "1_1") (pintype "passive"))
      (node (ref "J11") (pin "12") (pinfunction "12_12") (pintype "passive"))
      (node (ref "J4") (pin "6") (pinfunction "6_6") (pintype "passive"))
      (node (ref "J7") (pin "19L") (pinfunction "GND_19L") (pintype "passive"))
      (node (ref "J7") (pin "20L") (pinfunction "GND_20L") (pintype "passive"))
      (node (ref "J7") (pin "20R") (pinfunction "GND_20R") (pintype "passive"))
      (node (ref "J7") (pin "22L") (pinfunction "GND_22L") (pintype "passive"))
      (node (ref "J7") (pin "32R") (pinfunction "AGND_32R") (pintype "passive"))
      (node (ref "J7") (pin "8L") (pinfunction "GND_8L") (pintype "passive"))
      (node (ref "J7") (pin "9R") (pinfunction "GND_9R") (pintype "passive"))
      (node (ref "J9") (pin "1") (pinfunction "1_1") (pintype "passive"))
      (node (ref "Q1") (pin "3") (pinfunction "S_3") (pintype "passive"))
      (node (ref "Q2") (pin "3") (pinfunction "S_3") (pintype "passive"))
      (node (ref "Q3") (pin "3") (pinfunction "S_3") (pintype "passive"))
      (node (ref "R1") (pin "2") (pinfunction "2_2") (pintype "passive"))
      (node (ref "R5") (pin "1") (pinfunction "1_1") (pintype "passive"))
      (node (ref "R6") (pin "1") (pinfunction "1_1") (pintype "passive"))
      (node (ref "R7") (pin "1") (pinfunction "1_1") (pintype "passive"))
      (node (ref "TP8") (pin "1") (pinfunction "1_1") (pintype "passive"))
      (node (ref "TP9") (pin "1") (pinfunction "1_1") (pintype "passive"))
      (node (ref "U1") (pin "2") (pinfunction "VSS_2") (pintype "power_in"))
      (node (ref "U2") (pin "10") (pinfunction "GND_10") (pintype "power_in"))
    )
    (net (code "53") (name "Net-(C23-Pad2)") (class "Default")
      (node (ref "C23") (pin "2") (pinfunction "2_2") (pintype "passive"))
      (node (ref "R21") (pin "1") (pinfunction "1_1") (pintype "passive"))
    )
    (net (code "54") (name "Net-(C24-Pad2)") (class "Default")
      (node (ref "C24") (pin "2") (pinfunction "2_2") (pintype "passive"))
      (node (ref "R22") (pin "1") (pinfunction "1_1") (pintype "passive"))
    )
    (net (code "55") (name "Net-(C25-Pad2)") (class "Default")
      (node (ref "C25") (pin "2") (pinfunction "2_2") (pintype "passive"))
      (node (ref "R23") (pin "1") (pinfunction "1_1") (pintype "passive"))
    )
    (net (code "56") (name "Net-(D4-A)") (class "Default")
      (node (ref "D4") (pin "1") (pinfunction "A_1") (pintype "passive"))
      (node (ref "R2") (pin "1") (pinfunction "1_1") (pintype "passive"))
    )
    (net (code "57") (name "Net-(D5-A)") (class "Default")
      (node (ref "D5") (pin "1") (pinfunction "A_1") (pintype "passive"))
      (node (ref "R3") (pin "1") (pinfunction "1_1") (pintype "passive"))
    )
    (net (code "58") (name "Net-(D6-A)") (class "Default")
      (node (ref "D6") (pin "1") (pinfunction "A_1") (pintype "passive"))
      (node (ref "R4") (pin "1") (pinfunction "1_1") (pintype "passive"))
    )
    (net (code "59") (name "Net-(D7-A)") (class "Default")
      (node (ref "C23") (pin "1") (pinfunction "1_1") (pintype "passive"))
      (node (ref "D7") (pin "1") (pinfunction "A_1") (pintype "passive"))
      (node (ref "J12") (pin "5") (pinfunction "5_5") (pintype "passive"))
      (node (ref "Q1") (pin "2") (pinfunction "D_2") (pintype "passive"))
    )
    (net (code "60") (name "Net-(D8-A)") (class "Default")
      (node (ref "C24") (pin "1") (pinfunction "1_1") (pintype "passive"))
      (node (ref "D8") (pin "1") (pinfunction "A_1") (pintype "passive"))
      (node (ref "J12") (pin "3") (pinfunction "3_3") (pintype "passive"))
      (node (ref "Q2") (pin "2") (pinfunction "D_2") (pintype "passive"))
    )
    (net (code "61") (name "Net-(D9-A)") (class "Default")
      (node (ref "C25") (pin "1") (pinfunction "1_1") (pintype "passive"))
      (node (ref "D9") (pin "1") (pinfunction "A_1") (pintype "passive"))
      (node (ref "J12") (pin "1") (pinfunction "1_1") (pintype "passive"))
      (node (ref "Q3") (pin "2") (pinfunction "D_2") (pintype "passive"))
    )
    (net (code "62") (name "Net-(D10-A)") (class "Default")
      (node (ref "D10") (pin "1") (pinfunction "A_1") (pintype "passive"))
      (node (ref "R27") (pin "2") (pinfunction "2_2") (pintype "passive"))
    )
    (net (code "63") (name "Net-(D11-A)") (class "Default")
      (node (ref "D11") (pin "1") (pinfunction "A_1") (pintype "passive"))
      (node (ref "R28") (pin "1") (pinfunction "1_1") (pintype "passive"))
    )
    (net (code "64") (name "Net-(D12-A)") (class "Default")
      (node (ref "D12") (pin "1") (pinfunction "A_1") (pintype "passive"))
      (node (ref "R29") (pin "1") (pinfunction "1_1") (pintype "passive"))
    )
    (net (code "65") (name "Net-(F2-Pad2)") (class "Default")
      (node (ref "F2") (pin "2") (pinfunction "2_2") (pintype "passive"))
      (node (ref "J4") (pin "9") (pinfunction "9_9") (pintype "passive"))
    )
    (net (code "66") (name "Net-(J1-+)") (class "Default")
      (node (ref "F1") (pin "1") (pinfunction "1_1") (pintype "passive"))
      (node (ref "J1") (pin "1") (pinfunction "+_1") (pintype "passive"))
    )
    (net (code "67") (name "Net-(Q1-G)") (class "Default")
      (node (ref "Q1") (pin "1") (pinfunction "G_1") (pintype "passive"))
      (node (ref "R26") (pin "2") (pinfunction "2_2") (pintype "passive"))
      (node (ref "R5") (pin "2") (pinfunction "2_2") (pintype "passive"))
    )
    (net (code "68") (name "Net-(Q2-G)") (class "Default")
      (node (ref "Q2") (pin "1") (pinfunction "G_1") (pintype "passive"))
      (node (ref "R24") (pin "2") (pinfunction "2_2") (pintype "passive"))
      (node (ref "R6") (pin "2") (pinfunction "2_2") (pintype "passive"))
    )
    (net (code "69") (name "Net-(Q3-G)") (class "Default")
      (node (ref "Q3") (pin "1") (pinfunction "G_1") (pintype "passive"))
      (node (ref "R25") (pin "2") (pinfunction "2_2") (pintype "passive"))
      (node (ref "R7") (pin "2") (pinfunction "2_2") (pintype "passive"))
    )
    (net (code "70") (name "Net-(U1-RS)") (class "Default")
      (node (ref "R1") (pin "1") (pinfunction "1_1") (pintype "passive"))
      (node (ref "U1") (pin "8") (pinfunction "RS_8") (pintype "passive"))
    )
    (net (code "71") (name "unconnected-(J4-Pad1)") (class "Default")
      (node (ref "J4") (pin "1") (pinfunction "1_1") (pintype "passive+no_connect"))
    )
    (net (code "72") (name "unconnected-(J4-Pad3)") (class "Default")
      (node (ref "J4") (pin "3") (pinfunction "3_3") (pintype "passive+no_connect"))
    )
    (net (code "73") (name "unconnected-(J4-Pad4)") (class "Default")
      (node (ref "J4") (pin "4") (pinfunction "4_4") (pintype "passive+no_connect"))
    )
    (net (code "74") (name "unconnected-(J4-Pad5)") (class "Default")
      (node (ref "J4") (pin "5") (pinfunction "5_5") (pintype "passive+no_connect"))
    )
    (net (code "75") (name "unconnected-(J4-Pad8)") (class "Default")
      (node (ref "J4") (pin "8") (pinfunction "8_8") (pintype "passive+no_connect"))
    )
    (net (code "76") (name "unconnected-(J7A-BOOT0-Pad7L)") (class "Default")
      (node (ref "J7") (pin "7L") (pinfunction "BOOT0_7L") (pintype "passive+no_connect"))
    )
    (net (code "77") (name "unconnected-(J7A-IOREF-Pad12L)") (class "Default")
      (node (ref "J7") (pin "12L") (pinfunction "IOREF_12L") (pintype "passive+no_connect"))
    )
    (net (code "78") (name "unconnected-(J7A-NC-Pad9L)") (class "Default")
      (node (ref "J7") (pin "9L") (pinfunction "NC_9L") (pintype "passive+no_connect"))
    )
    (net (code "79") (name "unconnected-(J7A-NC-Pad10L)") (class "Default")
      (node (ref "J7") (pin "10L") (pinfunction "NC_10L") (pintype "passive+no_connect"))
    )
    (net (code "80") (name "unconnected-(J7A-NC-Pad11L)") (class "Default")
      (node (ref "J7") (pin "11L") (pinfunction "NC_11L") (pintype "passive+no_connect"))
    )
    (net (code "81") (name "unconnected-(J7A-NC-Pad26L)") (class "Default")
      (node (ref "J7") (pin "26L") (pinfunction "NC_26L") (pintype "passive+no_connect"))
    )
    (net (code "82") (name "unconnected-(J7A-PA0-Pad28L)") (class "Default")
      (node (ref "J7") (pin "28L") (pinfunction "PA0_28L") (pintype "passive+no_connect"))
    )
    (net (code "83") (name "unconnected-(J7A-PA13-Pad13L)") (class "Default")
      (node (ref "J7") (pin "13L") (pinfunction "PA13_13L") (pintype "passive+no_connect"))
    )
    (net (code "84") (name "unconnected-(J7A-PA14-Pad15L)") (class "Default")
      (node (ref "J7") (pin "15L") (pinfunction "PA14_15L") (pintype "passive+no_connect"))
    )
    (net (code "85") (name "unconnected-(J7A-PA15-Pad17L)") (class "Default")
      (node (ref "J7") (pin "17L") (pinfunction "PA15_17L") (pintype "passive+no_connect"))
    )
    (net (code "86") (name "unconnected-(J7A-PC13-Pad23L)") (class "Default")
      (node (ref "J7") (pin "23L") (pinfunction "PC13_23L") (pintype "passive+no_connect"))
    )
    (net (code "87") (name "unconnected-(J7A-PC14-Pad25L)") (class "Default")
      (node (ref "J7") (pin "25L") (pinfunction "PC14_25L") (pintype "passive+no_connect"))
    )
    (net (code "88") (name "unconnected-(J7A-PC15-Pad27L)") (class "Default")
      (node (ref "J7") (pin "27L") (pinfunction "PC15_27L") (pintype "passive+no_connect"))
    )
    (net (code "89") (name "unconnected-(J7A-PD0-Pad29L)") (class "Default")
      (node (ref "J7") (pin "29L") (pinfunction "PD0_29L") (pintype "passive+no_connect"))
    )
    (net (code "90") (name "unconnected-(J7A-PD1-Pad31L)") (class "Default")
      (node (ref "J7") (pin "31L") (pinfunction "PD1_31L") (pintype "passive+no_connect"))
    )
    (net (code "91") (name "unconnected-(J7A-RESET-Pad14L)") (class "Default")
      (node (ref "J7") (pin "14L") (pinfunction "RESET_14L") (pintype "passive+no_connect"))
    )
    (net (code "92") (name "unconnected-(J7A-VBAT-Pad33L)") (class "Default")
      (node (ref "J7") (pin "33L") (pinfunction "VBAT_33L") (pintype "passive+no_connect"))
    )
    (net (code "93") (name "unconnected-(J7A-VDD-Pad5L)") (class "Default")
      (node (ref "J7") (pin "5L") (pinfunction "VDD_5L") (pintype "passive+no_connect"))
    )
    (net (code "94") (name "unconnected-(J7B-AVDD-Pad7R)") (class "Default")
      (node (ref "J7") (pin "7R") (pinfunction "AVDD_7R") (pintype "passive+no_connect"))
    )
    (net (code "95") (name "unconnected-(J7B-NC-Pad10R)") (class "Default")
      (node (ref "J7") (pin "10R") (pinfunction "NC_10R") (pintype "passive+no_connect"))
    )
    (net (code "96") (name "unconnected-(J7B-NC-Pad36R)") (class "Default")
      (node (ref "J7") (pin "36R") (pinfunction "NC_36R") (pintype "passive+no_connect"))
    )
    (net (code "97") (name "unconnected-(J7B-NC-Pad38R)") (class "Default")
      (node (ref "J7") (pin "38R") (pinfunction "NC_38R") (pintype "passive+no_connect"))
    )
    (net (code "98") (name "unconnected-(J7B-PA2-Pad35R)") (class "Default")
      (node (ref "J7") (pin "35R") (pinfunction "PA2_35R") (pintype "passive+no_connect"))
    )
    (net (code "99") (name "unconnected-(J7B-PA3-Pad37R)") (class "Default")
      (node (ref "J7") (pin "37R") (pinfunction "PA3_37R") (pintype "passive+no_connect"))
    )
    (net (code "100") (name "unconnected-(J7B-PA8-Pad23R)") (class "Default")
      (node (ref "J7") (pin "23R") (pinfunction "PA8_23R") (pintype "passive+no_connect"))
    )
    (net (code "101") (name "unconnected-(J7B-PA9-Pad21R)") (class "Default")
      (node (ref "J7") (pin "21R") (pinfunction "PA9_21R") (pintype "passive+no_connect"))
    )
    (net (code "102") (name "unconnected-(J7B-PA10-Pad33R)") (class "Default")
      (node (ref "J7") (pin "33R") (pinfunction "PA10_33R") (pintype "passive+no_connect"))
    )
    (net (code "103") (name "unconnected-(J7B-PB3-Pad31R)") (class "Default")
      (node (ref "J7") (pin "31R") (pinfunction "PB3_31R") (pintype "passive+no_connect"))
    )
    (net (code "104") (name "unconnected-(J7B-PB4-Pad27R)") (class "Default")
      (node (ref "J7") (pin "27R") (pinfunction "PB4_27R") (pintype "passive+no_connect"))
    )
    (net (code "105") (name "unconnected-(J7B-PB5-Pad29R)") (class "Default")
      (node (ref "J7") (pin "29R") (pinfunction "PB5_29R") (pintype "passive+no_connect"))
    )
    (net (code "106") (name "unconnected-(J7B-PB8-Pad3R)") (class "Default")
      (node (ref "J7") (pin "3R") (pinfunction "PB8_3R") (pintype "passive+no_connect"))
    )
    (net (code "107") (name "unconnected-(J7B-PB9-Pad5R)") (class "Default")
      (node (ref "J7") (pin "5R") (pinfunction "PB9_5R") (pintype "passive+no_connect"))
    )
    (net (code "108") (name "unconnected-(J7B-PB10-Pad25R)") (class "Default")
      (node (ref "J7") (pin "25R") (pinfunction "PB10_25R") (pintype "passive+no_connect"))
    )
    (net (code "109") (name "unconnected-(J7B-PB13-Pad30R)") (class "Default")
      (node (ref "J7") (pin "30R") (pinfunction "PB13_30R") (pintype "passive+no_connect"))
    )
    (net (code "110") (name "unconnected-(J7B-PB14-Pad28R)") (class "Default")
      (node (ref "J7") (pin "28R") (pinfunction "PB14_28R") (pintype "passive+no_connect"))
    )
    (net (code "111") (name "unconnected-(J7B-PB15-Pad26R)") (class "Default")
      (node (ref "J7") (pin "26R") (pinfunction "PB15_26R") (pintype "passive+no_connect"))
    )
    (net (code "112") (name "unconnected-(J7B-U5V-Pad8R)") (class "Default")
      (node (ref "J7") (pin "8R") (pinfunction "U5V_8R") (pintype "passive+no_connect"))
    )
    (net (code "113") (name "unconnected-(J11-Pad13)") (class "Default")
      (node (ref "J11") (pin "13") (pinfunction "13_13") (pintype "passive+no_connect"))
    )
    (net (code "114") (name "unconnected-(U1-VREF-Pad5)") (class "Default")
      (node (ref "U1") (pin "5") (pinfunction "VREF_5") (pintype "output+no_connect"))
    )
    (net (code "115") (name "unconnected-(U2-REF_+-Pad14)") (class "Default")
      (node (ref "U2") (pin "14") (pinfunction "REF_+_14") (pintype "bidirectional+no_connect"))
    )
    (net (code "116") (name "unconnected-(U2-REF_--Pad13)") (class "Default")
      (node (ref "U2") (pin "13") (pinfunction "REF_-_13") (pintype "bidirectional+no_connect"))
    )
  )
)
